# ESC.net
KiCad netlist of a schematic drawn in Altium Designer
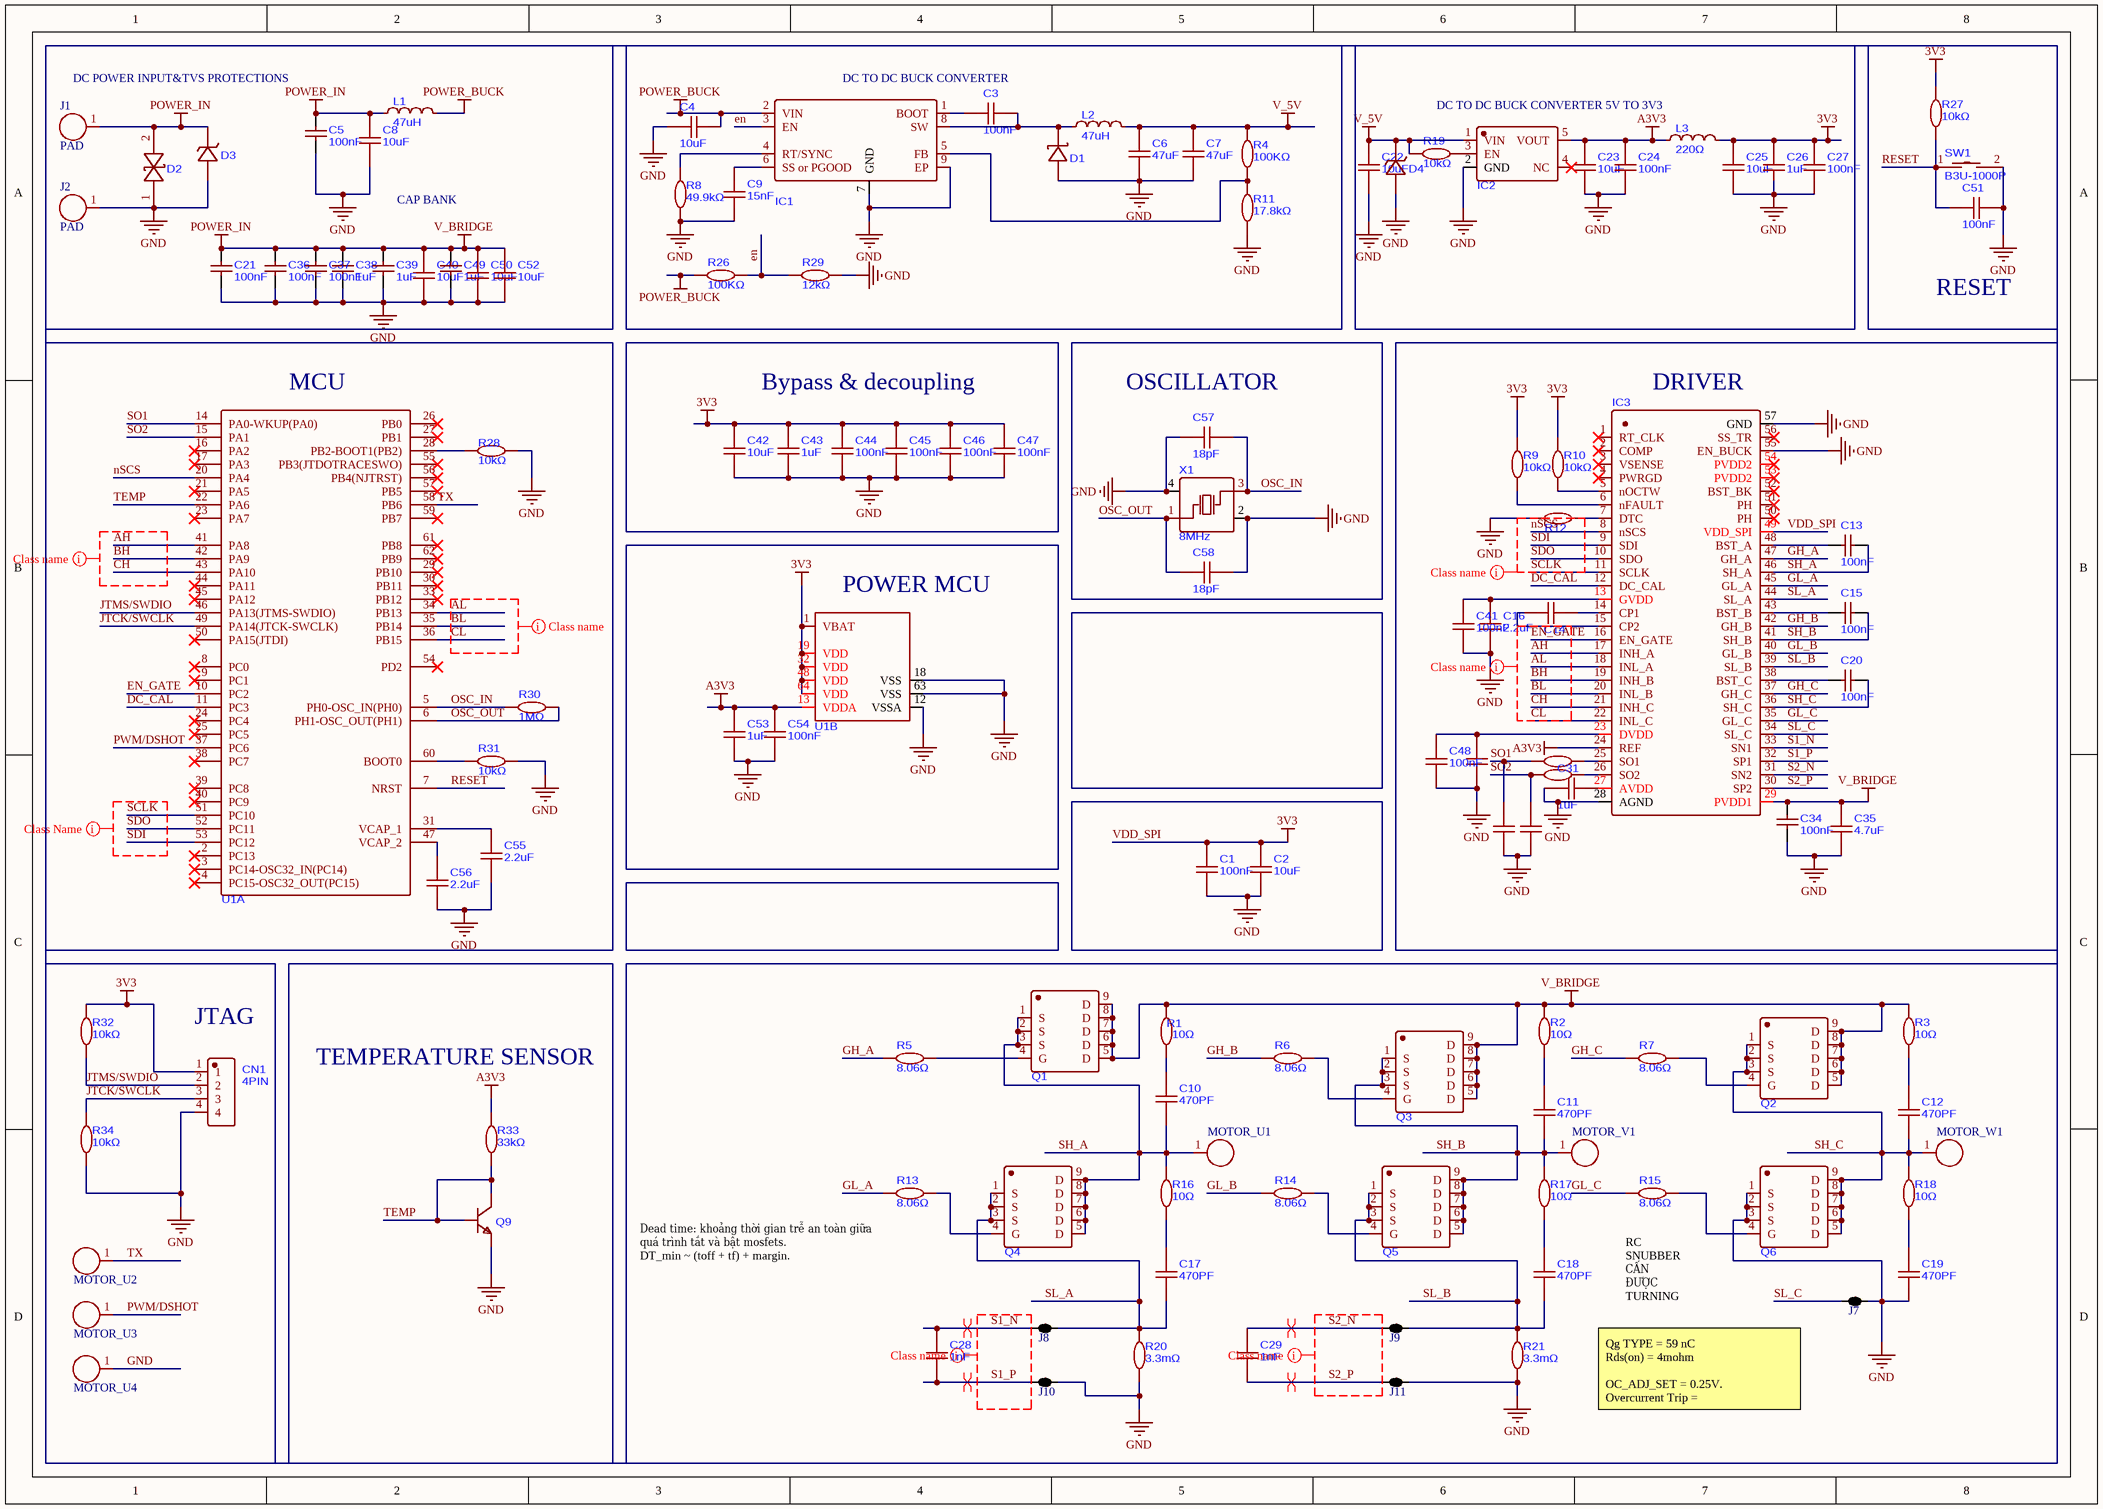
[diagram p0: ESC.SchDoc]

(export (version "E")
  (design (tool "Eeschema 10.0.6"))
  (components
    (comp (ref "C1")
      (value "100nF")
      (footprint "C0603")
      (description "100nF ±10% 50V Ceramic Capacitor X7R 0603")
      (libsource (lib "ESC") (part "CC0603KRX7R9BB104"))
    )
    (comp (ref "C2")
      (value "10uF")
      (footprint "C0603")
      (description "10uF ±10% 10V Ceramic Capacitor X5R 0603")
      (libsource (lib "ESC") (part "CL10A106KP8NNNC"))
    )
    (comp (ref "C3")
      (value "100nF")
      (footprint "C0603")
      (description "100nF ±10% 50V Ceramic Capacitor X7R 0603")
      (libsource (lib "ESC") (part "CC0603KRX7R9BB104"))
    )
    (comp (ref "C4")
      (value "10uF")
      (footprint "C1206")
      (description "10uF X6S ±10% 100V 1206 Ceramic Capacitors RoHS")
      (libsource (lib "ESC") (part "C3216X6S2A106KT0A0E"))
    )
    (comp (ref "C5")
      (value "100nF")
      (footprint "C0805")
      (description "100nF ±10% 100V Ceramic Capacitor X7R 0805")
      (libsource (lib "ESC") (part "CL21B104KCFNNNE"))
    )
    (comp (ref "C6")
      (value "47uF")
      (footprint "C0603")
      (description "47uF ±20% 10V Ceramic Capacitor X5R 0805")
      (libsource (lib "ESC") (part "GRM21BR61A476ME15L_1"))
    )
    (comp (ref "C7")
      (value "47uF")
      (footprint "C0603")
      (description "47uF ±20% 10V Ceramic Capacitor X5R 0805")
      (libsource (lib "ESC") (part "GRM21BR61A476ME15L_1"))
    )
    (comp (ref "C8")
      (value "10uF")
      (footprint "C1206")
      (description "10uF X6S ±10% 100V 1206 Ceramic Capacitors RoHS")
      (libsource (lib "ESC") (part "C3216X6S2A106KT0A0E"))
    )
    (comp (ref "C9")
      (value "15nF")
      (footprint "C0603")
      (description "10uF ±10% 10V Ceramic Capacitor X5R 0603")
      (libsource (lib "ESC") (part "CC0603KRX7R9BB153"))
    )
    (comp (ref "C10")
      (value "470PF")
      (footprint "C0805")
      (description "10nF ±10% 100V Ceramic Capacitor X7R 0805")
      (libsource (lib "ESC") (part "CC0805KRX7R0BB103"))
    )
    (comp (ref "C11")
      (value "470PF")
      (footprint "C0805")
      (description "10nF ±10% 100V Ceramic Capacitor X7R 0805")
      (libsource (lib "ESC") (part "CC0805KRX7R0BB103"))
    )
    (comp (ref "C12")
      (value "470PF")
      (footprint "C0805")
      (description "10nF ±10% 100V Ceramic Capacitor X7R 0805")
      (libsource (lib "ESC") (part "CC0805KRX7R0BB103"))
    )
    (comp (ref "C13")
      (value "100nF")
      (footprint "C0805")
      (description "100nF ±10% 100V Ceramic Capacitor X7R 0805")
      (libsource (lib "ESC") (part "CL21B104KCFNNNE"))
    )
    (comp (ref "C14")
      (value "220nF")
      (footprint "C0603")
      (description "220nF ±10% 25V Ceramic Capacitor X7R 0603")
      (libsource (lib "ESC") (part "CL10B224KA8NNNC"))
    )
    (comp (ref "C15")
      (value "100nF")
      (footprint "C0805")
      (description "100nF ±10% 100V Ceramic Capacitor X7R 0805")
      (libsource (lib "ESC") (part "CL21B104KCFNNNE"))
    )
    (comp (ref "C16")
      (value "2.2uF")
      (footprint "C0603")
      (description "2.2uF X5R ±10% 25V 0603 Ceramic Capacitors RoHS")
      (libsource (lib "ESC") (part "CC0603X5R25V225KN"))
    )
    (comp (ref "C17")
      (value "470PF")
      (footprint "C0805")
      (description "10nF ±10% 100V Ceramic Capacitor X7R 0805")
      (libsource (lib "ESC") (part "CC0805KRX7R0BB103"))
    )
    (comp (ref "C18")
      (value "470PF")
      (footprint "C0805")
      (description "10nF ±10% 100V Ceramic Capacitor X7R 0805")
      (libsource (lib "ESC") (part "CC0805KRX7R0BB103"))
    )
    (comp (ref "C19")
      (value "470PF")
      (footprint "C0805")
      (description "10nF ±10% 100V Ceramic Capacitor X7R 0805")
      (libsource (lib "ESC") (part "CC0805KRX7R0BB103"))
    )
    (comp (ref "C20")
      (value "100nF")
      (footprint "C0805")
      (description "100nF ±10% 100V Ceramic Capacitor X7R 0805")
      (libsource (lib "ESC") (part "CL21B104KCFNNNE"))
    )
    (comp (ref "C21")
      (value "100nF")
      (footprint "C0805")
      (description "100nF ±10% 100V Ceramic Capacitor X7R 0805")
      (libsource (lib "ESC") (part "CL21B104KCFNNNE"))
    )
    (comp (ref "C22")
      (value "10uF")
      (footprint "C0603")
      (description "10uF ±10% 10V Ceramic Capacitor X5R 0603")
      (libsource (lib "ESC") (part "CL10A106KP8NNNC"))
    )
    (comp (ref "C23")
      (value "10uF")
      (footprint "C0603")
      (description "10uF ±10% 10V Ceramic Capacitor X5R 0603")
      (libsource (lib "ESC") (part "CL10A106KP8NNNC"))
    )
    (comp (ref "C24")
      (value "100nF")
      (footprint "C0603")
      (description "100nF ±10% 50V Ceramic Capacitor X7R 0603")
      (libsource (lib "ESC") (part "CC0603KRX7R9BB104"))
    )
    (comp (ref "C25")
      (value "10uF")
      (footprint "C0603")
      (description "10uF ±10% 10V Ceramic Capacitor X5R 0603")
      (libsource (lib "ESC") (part "CL10A106KP8NNNC"))
    )
    (comp (ref "C26")
      (value "1uF")
      (footprint "C0603")
      (description "1uF ±10% 25V Ceramic Capacitor X7R 0603")
      (libsource (lib "ESC") (part "CL10B105KA8NNNC"))
    )
    (comp (ref "C27")
      (value "100nF")
      (footprint "C0603")
      (description "100nF ±10% 50V Ceramic Capacitor X7R 0603")
      (libsource (lib "ESC") (part "CC0603KRX7R9BB104"))
    )
    (comp (ref "C28")
      (value "1nF")
      (footprint "C0603")
      (description "1nF ±10% 50V Ceramic Capacitor X7R 0603")
      (libsource (lib "ESC") (part "CC0603KRX7R9BB102"))
    )
    (comp (ref "C29")
      (value "1nF")
      (footprint "C0603")
      (description "1nF ±10% 50V Ceramic Capacitor X7R 0603")
      (libsource (lib "ESC") (part "CC0603KRX7R9BB102"))
    )
    (comp (ref "C30")
      (value "1uF")
      (footprint "C0603")
      (description "1uF ±10% 25V Ceramic Capacitor X7R 0603")
      (libsource (lib "ESC") (part "CL10B105KA8NNNC"))
    )
    (comp (ref "C31")
      (value "1uF")
      (footprint "C0603")
      (description "1uF ±10% 25V Ceramic Capacitor X7R 0603")
      (libsource (lib "ESC") (part "CL10B105KA8NNNC"))
    )
    (comp (ref "C32")
      (value "2.2uF")
      (footprint "C0603")
      (description "2.2uF X5R ±10% 25V 0603 Ceramic Capacitors RoHS")
      (libsource (lib "ESC") (part "CC0603X5R25V225KN"))
    )
    (comp (ref "C33")
      (value "2.2uF")
      (footprint "C0603")
      (description "2.2uF X5R ±10% 25V 0603 Ceramic Capacitors RoHS")
      (libsource (lib "ESC") (part "CC0603X5R25V225KN"))
    )
    (comp (ref "C34")
      (value "100nF")
      (footprint "C0805")
      (description "100nF ±10% 100V Ceramic Capacitor X7R 0805")
      (libsource (lib "ESC") (part "CL21B104KCFNNNE"))
    )
    (comp (ref "C35")
      (value "4.7uF")
      (footprint "C0805")
      (description "4.7uF ±10% 100V Ceramic Capacitor X5R 0805")
      (libsource (lib "ESC") (part "CIA0805X5R475K101MT"))
    )
    (comp (ref "C36")
      (value "100nF")
      (footprint "C0805")
      (description "100nF ±10% 100V Ceramic Capacitor X7R 0805")
      (libsource (lib "ESC") (part "CL21B104KCFNNNE"))
    )
    (comp (ref "C37")
      (value "100nF")
      (footprint "C0805")
      (description "100nF ±10% 100V Ceramic Capacitor X7R 0805")
      (libsource (lib "ESC") (part "CL21B104KCFNNNE"))
    )
    (comp (ref "C38")
      (value "1uF")
      (footprint "C0805")
      (description "1uF ±10% 100V Ceramic Capacitor X7R 0805")
      (libsource (lib "ESC") (part "CGA0805X7R105K101MT"))
    )
    (comp (ref "C39")
      (value "1uF")
      (footprint "C0805")
      (description "1uF ±10% 100V Ceramic Capacitor X7R 0805")
      (libsource (lib "ESC") (part "CGA0805X7R105K101MT"))
    )
    (comp (ref "C40")
      (value "10uF")
      (footprint "C1206")
      (description "10uF X6S ±10% 100V 1206 Ceramic Capacitors RoHS")
      (libsource (lib "ESC") (part "C3216X6S2A106KT0A0E"))
    )
    (comp (ref "C41")
      (value "100nF")
      (footprint "C0603")
      (description "100nF ±10% 50V Ceramic Capacitor X7R 0603")
      (libsource (lib "ESC") (part "CC0603KRX7R9BB104"))
    )
    (comp (ref "C42")
      (value "10uF")
      (footprint "C0603")
      (description "10uF ±10% 10V Ceramic Capacitor X5R 0603")
      (libsource (lib "ESC") (part "CL10A106KP8NNNC"))
    )
    (comp (ref "C43")
      (value "1uF")
      (footprint "C0603")
      (description "1uF ±10% 25V Ceramic Capacitor X7R 0603")
      (libsource (lib "ESC") (part "CL10B105KA8NNNC"))
    )
    (comp (ref "C44")
      (value "100nF")
      (footprint "C0603")
      (description "100nF ±10% 50V Ceramic Capacitor X7R 0603")
      (libsource (lib "ESC") (part "CC0603KRX7R9BB104"))
    )
    (comp (ref "C45")
      (value "100nF")
      (footprint "C0603")
      (description "100nF ±10% 50V Ceramic Capacitor X7R 0603")
      (libsource (lib "ESC") (part "CC0603KRX7R9BB104"))
    )
    (comp (ref "C46")
      (value "100nF")
      (footprint "C0603")
      (description "100nF ±10% 50V Ceramic Capacitor X7R 0603")
      (libsource (lib "ESC") (part "CC0603KRX7R9BB104"))
    )
    (comp (ref "C47")
      (value "100nF")
      (footprint "C0603")
      (description "100nF ±10% 50V Ceramic Capacitor X7R 0603")
      (libsource (lib "ESC") (part "CC0603KRX7R9BB104"))
    )
    (comp (ref "C48")
      (value "100nF")
      (footprint "C0603")
      (description "100nF ±10% 50V Ceramic Capacitor X7R 0603")
      (libsource (lib "ESC") (part "CC0603KRX7R9BB104"))
    )
    (comp (ref "C49")
      (value "1uF")
      (footprint "C0805")
      (description "1uF ±10% 100V Ceramic Capacitor X7R 0805")
      (libsource (lib "ESC") (part "CGA0805X7R105K101MT"))
    )
    (comp (ref "C50")
      (value "10uF")
      (footprint "C1206")
      (description "10uF X6S ±10% 100V 1206 Ceramic Capacitors RoHS")
      (libsource (lib "ESC") (part "C3216X6S2A106KT0A0E"))
    )
    (comp (ref "C51")
      (value "100nF")
      (footprint "C0603")
      (description "100nF ±10% 50V Ceramic Capacitor X7R 0603")
      (libsource (lib "ESC") (part "CC0603KRX7R9BB104"))
    )
    (comp (ref "C52")
      (value "10uF")
      (footprint "C1206")
      (description "10uF X6S ±10% 100V 1206 Ceramic Capacitors RoHS")
      (libsource (lib "ESC") (part "C3216X6S2A106KT0A0E"))
    )
    (comp (ref "C53")
      (value "1uF")
      (footprint "C0603")
      (description "1uF ±10% 25V Ceramic Capacitor X7R 0603")
      (libsource (lib "ESC") (part "CL10B105KA8NNNC"))
    )
    (comp (ref "C54")
      (value "100nF")
      (footprint "C0603")
      (description "100nF ±10% 50V Ceramic Capacitor X7R 0603")
      (libsource (lib "ESC") (part "CC0603KRX7R9BB104"))
    )
    (comp (ref "C55")
      (value "2.2uF")
      (footprint "C0603")
      (description "2.2uF X5R ±10% 25V 0603 Ceramic Capacitors RoHS")
      (libsource (lib "ESC") (part "CC0603X5R25V225KN"))
    )
    (comp (ref "C56")
      (value "2.2uF")
      (footprint "C0603")
      (description "2.2uF X5R ±10% 25V 0603 Ceramic Capacitors RoHS")
      (libsource (lib "ESC") (part "CC0603X5R25V225KN"))
    )
    (comp (ref "C57")
      (value "18pF")
      (footprint "C0603")
      (description "18pF ±5% 50V Ceramic Capacitor C0G 0603")
      (libsource (lib "ESC") (part "CL10C180JB8NNNC"))
    )
    (comp (ref "C58")
      (value "18pF")
      (footprint "C0603")
      (description "18pF ±5% 50V Ceramic Capacitor C0G 0603")
      (libsource (lib "ESC") (part "CL10C180JB8NNNC"))
    )
    (comp (ref "CN1")
      (value "4PIN")
      (footprint "HDR-TH_4P-HX-PH254-01-04-Z-L11.5")
      (libsource (lib "ESC") (part "HX PH254-01-04-Z-L11.5 STRAIGHT PIN HEADER"))
    )
    (comp (ref "D1")
      (value "DIODE SCHOTTKY 100V SMA(DO-214AC)")
      (footprint "SMA_L4.3-W2.6-LS5.2-RD")
      (description "Diode 100V 2A Surface Mount SMA(DO-214AC)")
      (libsource (lib "ESC") (part "SS210"))
    )
    (comp (ref "D2")
      (value "TVS DIODE 54VWM 87.1VC DO-214AB(SMCJ)")
      (footprint "SMB_L4.6-W3.6-LS5.3-BI")
      (description "87.1VC Clamp 17.2A Ipp TVS DIODE DO-214AB(SMCJ)")
      (libsource (lib "ESC") (part "VISHAY SMCJ54A-E3/57T"))
    )
    (comp (ref "D3")
      (value "DIODE ZENER 56V 500mW SOD-123W")
      (footprint "SOD-123_L2.8-W1.8-LS3.7-RD")
      (description "Zener Diode Independent 56V 500mW Surface Mount SOD-123W")
      (libsource (lib "ESC") (part "BZT52C56"))
    )
    (comp (ref "D4")
      (value "DIODE ZENER 5.6V 500mW LL-34")
      (footprint "LL-34_L3.5-W1.5-RD")
      (description "Zener Diode Independent 5.6V 500mW Surface Mount LL-34")
      (libsource (lib "ESC") (part "ZMM5V6_C707195"))
    )
    (comp (ref "IC1")
      (value "60V 3A Step-Down Converter")
      (footprint "SOIC-8_L4.9-W3.9-P1.27-LS6.0-BL-EP2.3")
      (libsource (lib "ESC") (part "LMR16030SDDAR"))
    )
    (comp (ref "IC2")
      (value "500mA Low-Noise LDo Voltage Regulator")
      (footprint "SOT-23-5_L2.9-W1.6-P0.95-LS2.8-BR")
      (description "3.3V 16V Positive Fixed SOT-23-5 Voltage Regulators - Linear, Low Drop Out (LDO) Regulators RoHS")
      (libsource (lib "ESC") (part "SPX3819M5-L-3-3"))
    )
    (comp (ref "IC3")
      (value "DRV8301 Three-Phase Gate Driver With Dual Current Shunt Amplifiers and Buck Regulator")
      (footprint "HTSSOP-56_L14.0-W6.0-P0.50-LS8.1-BL-EP")
      (description "MOSFET 1.7A 2.3A HTSSOP-56-EP-6mm Motor Drivers, Controllers RoHS")
      (libsource (lib "ESC") (part "DRV8301DCA"))
    )
    (comp (ref "J1") (value "PAD") (footprint "PAD") (libsource (lib "ESC") (part "PAD")))
    (comp (ref "J2") (value "PAD") (footprint "PAD") (libsource (lib "ESC") (part "PAD")))
    (comp (ref "J7")
      (value "2 way net tie junction")
      (footprint "2way_LP")
      (libsource (lib "ESC") (part "2way"))
    )
    (comp (ref "J8")
      (value "2 way net tie junction")
      (footprint "2way_LP")
      (libsource (lib "ESC") (part "2way"))
    )
    (comp (ref "J9")
      (value "2 way net tie junction")
      (footprint "2way_LP")
      (libsource (lib "ESC") (part "2way"))
    )
    (comp (ref "J10")
      (value "2 way net tie junction")
      (footprint "2way_LP")
      (libsource (lib "ESC") (part "2way"))
    )
    (comp (ref "J11")
      (value "2 way net tie junction")
      (footprint "2way_LP")
      (libsource (lib "ESC") (part "2way"))
    )
    (comp (ref "L1")
      (value "47uH")
      (footprint "IND-SMD_L5.0-W5.0_FNR50XXS")
      (description "1.15A 47uH ±20% 1.2A 354mΩ Magnetic Shielded Inductor SMD,5x5mm Fixed Inductors RoHS")
      (libsource (lib "ESC") (part "FNR5040S470MT"))
    )
    (comp (ref "L2")
      (value "47uH")
      (footprint "IND-SMD_L5.0-W5.0_FNR50XXS")
      (description "1.15A 47uH ±20% 1.2A 354mΩ Magnetic Shielded Inductor SMD,5x5mm Fixed Inductors RoHS")
      (libsource (lib "ESC") (part "FNR5040S470MT"))
    )
    (comp (ref "L3")
      (value "220Ω")
      (footprint "C0805")
      (description "220Ω@100MHz 1 Line Ferrite Bead 0805 2A 45mΩ")
      (libsource (lib "ESC") (part "BLM21PG221SN1D"))
    )
    (comp (ref "MOTOR_U1") (value "PAD") (footprint "PAD") (libsource (lib "ESC") (part "PAD")))
    (comp (ref "MOTOR_U2") (value "PAD") (footprint "PAD") (libsource (lib "ESC") (part "PAD")))
    (comp (ref "MOTOR_U3") (value "PAD") (footprint "PAD") (libsource (lib "ESC") (part "PAD")))
    (comp (ref "MOTOR_U4") (value "PAD") (footprint "PAD") (libsource (lib "ESC") (part "PAD")))
    (comp (ref "MOTOR_V1") (value "PAD") (footprint "PAD") (libsource (lib "ESC") (part "PAD")))
    (comp (ref "MOTOR_W1") (value "PAD") (footprint "PAD") (libsource (lib "ESC") (part "PAD")))
    (comp (ref "Q1")
      (value "MOSFET N-CH 80V 100A SOP-8-Advance")
      (footprint "SOP-8_L5.0-W5.0-P1.27-LS6.0_TPH4R008NH-L1Q")
      (description "N-Channel 80V 100A 78W SOP-8-Advance")
      (libsource (lib "ESC") (part "TPH4R008NH,L1Q(M"))
    )
    (comp (ref "Q2")
      (value "MOSFET N-CH 80V 100A SOP-8-Advance")
      (footprint "SOP-8_L5.0-W5.0-P1.27-LS6.0_TPH4R008NH-L1Q")
      (description "N-Channel 80V 100A 78W SOP-8-Advance")
      (libsource (lib "ESC") (part "TPH4R008NH,L1Q(M"))
    )
    (comp (ref "Q3")
      (value "MOSFET N-CH 80V 100A SOP-8-Advance")
      (footprint "SOP-8_L5.0-W5.0-P1.27-LS6.0_TPH4R008NH-L1Q")
      (description "N-Channel 80V 100A 78W SOP-8-Advance")
      (libsource (lib "ESC") (part "TPH4R008NH,L1Q(M"))
    )
    (comp (ref "Q4")
      (value "MOSFET N-CH 80V 100A SOP-8-Advance")
      (footprint "SOP-8_L5.0-W5.0-P1.27-LS6.0_TPH4R008NH-L1Q")
      (description "N-Channel 80V 100A 78W SOP-8-Advance")
      (libsource (lib "ESC") (part "TPH4R008NH,L1Q(M"))
    )
    (comp (ref "Q5")
      (value "MOSFET N-CH 80V 100A SOP-8-Advance")
      (footprint "SOP-8_L5.0-W5.0-P1.27-LS6.0_TPH4R008NH-L1Q")
      (description "N-Channel 80V 100A 78W SOP-8-Advance")
      (libsource (lib "ESC") (part "TPH4R008NH,L1Q(M"))
    )
    (comp (ref "Q6")
      (value "MOSFET N-CH 80V 100A SOP-8-Advance")
      (footprint "SOP-8_L5.0-W5.0-P1.27-LS6.0_TPH4R008NH-L1Q")
      (description "N-Channel 80V 100A 78W SOP-8-Advance")
      (libsource (lib "ESC") (part "TPH4R008NH,L1Q(M"))
    )
    (comp (ref "Q9")
      (value "TRANS NPN 40V 200mA SOT-416")
      (footprint "SC-75-3_L1.6-W0.8-P1.00-LS1.6-BR")
      (description "Bipolar (BJT) Transistor NPN 40V 200mA 300MHz 200mW Surface Mount SOT-416")
      (libsource (lib "ESC") (part "MMBT3904TT1G"))
    )
    (comp (ref "R1")
      (value "10Ω")
      (footprint "R0805")
      (description "10Ω 500mW Thick Film Resistor ±100ppm/℃ ±1% 0805 Chip Resistor - Surface Mount RoHS")
      (libsource (lib "ESC") (part "CRCW080510R0FKEAHP"))
    )
    (comp (ref "R2")
      (value "10Ω")
      (footprint "R0805")
      (description "10Ω 500mW Thick Film Resistor ±100ppm/℃ ±1% 0805 Chip Resistor - Surface Mount RoHS")
      (libsource (lib "ESC") (part "CRCW080510R0FKEAHP"))
    )
    (comp (ref "R3")
      (value "10Ω")
      (footprint "R0805")
      (description "10Ω 500mW Thick Film Resistor ±100ppm/℃ ±1% 0805 Chip Resistor - Surface Mount RoHS")
      (libsource (lib "ESC") (part "CRCW080510R0FKEAHP"))
    )
    (comp (ref "R4")
      (value "100KΩ")
      (footprint "R0603")
      (description "100mW 100kΩ 75V Thick Film Resistor ±100ppm/℃ ±1% 0603 Chip Resistor - Surface Mount RoHS")
      (libsource (lib "ESC") (part "RC0603FR-07100KL"))
    )
    (comp (ref "R5")
      (value "8.06Ω")
      (footprint "R1206")
      (description "8.06Ω ±1% 250mW 1206 Thick Film Resistor")
      (libsource (lib "ESC") (part "FRC1206F8R06TS"))
    )
    (comp (ref "R6")
      (value "8.06Ω")
      (footprint "R1206")
      (description "8.06Ω ±1% 250mW 1206 Thick Film Resistor")
      (libsource (lib "ESC") (part "FRC1206F8R06TS"))
    )
    (comp (ref "R7")
      (value "8.06Ω")
      (footprint "R1206")
      (description "8.06Ω ±1% 250mW 1206 Thick Film Resistor")
      (libsource (lib "ESC") (part "FRC1206F8R06TS"))
    )
    (comp (ref "R8")
      (value "49.9kΩ")
      (footprint "R0603")
      (description "100mW 49.9kΩ 75V Thick Film Resistor ±100ppm/℃ ±1% 0603 Chip Resistor - Surface Mount RoHS")
      (libsource (lib "ESC") (part "RC0603FR-0749K9L"))
    )
    (comp (ref "R9")
      (value "10kΩ")
      (footprint "R0603")
      (description "100mW 10kΩ 75V ±100ppm/℃ Thick Film Resistor ±1% 0603 Chip Resistor - Surface Mount ROHS")
      (libsource (lib "ESC") (part "RC0603FR-0710KL"))
    )
    (comp (ref "R10")
      (value "10kΩ")
      (footprint "R0603")
      (description "100mW 10kΩ 75V ±100ppm/℃ Thick Film Resistor ±1% 0603 Chip Resistor - Surface Mount ROHS")
      (libsource (lib "ESC") (part "RC0603FR-0710KL"))
    )
    (comp (ref "R11")
      (value "17.8kΩ")
      (footprint "R0603")
      (description "17.8kΩ ±1% 100mW 0603 Thick Film Resistor")
      (libsource (lib "ESC") (part "0603WAF1782T5E"))
    )
    (comp (ref "R12")
      (value "24.9KΩ")
      (footprint "R0603")
      (description "24.9kΩ ±1% 100mW 0603 Thick Film Resistor")
      (libsource (lib "ESC") (part "FRC0603F2492TS"))
    )
    (comp (ref "R13")
      (value "8.06Ω")
      (footprint "R1206")
      (description "8.06Ω ±1% 250mW 1206 Thick Film Resistor")
      (libsource (lib "ESC") (part "FRC1206F8R06TS"))
    )
    (comp (ref "R14")
      (value "8.06Ω")
      (footprint "R1206")
      (description "8.06Ω ±1% 250mW 1206 Thick Film Resistor")
      (libsource (lib "ESC") (part "FRC1206F8R06TS"))
    )
    (comp (ref "R15")
      (value "8.06Ω")
      (footprint "R1206")
      (description "8.06Ω ±1% 250mW 1206 Thick Film Resistor")
      (libsource (lib "ESC") (part "FRC1206F8R06TS"))
    )
    (comp (ref "R16")
      (value "10Ω")
      (footprint "R0805")
      (description "10Ω 500mW Thick Film Resistor ±100ppm/℃ ±1% 0805 Chip Resistor - Surface Mount RoHS")
      (libsource (lib "ESC") (part "CRCW080510R0FKEAHP"))
    )
    (comp (ref "R17")
      (value "10Ω")
      (footprint "R0805")
      (description "10Ω 500mW Thick Film Resistor ±100ppm/℃ ±1% 0805 Chip Resistor - Surface Mount RoHS")
      (libsource (lib "ESC") (part "CRCW080510R0FKEAHP"))
    )
    (comp (ref "R18")
      (value "10Ω")
      (footprint "R0805")
      (description "10Ω 500mW Thick Film Resistor ±100ppm/℃ ±1% 0805 Chip Resistor - Surface Mount RoHS")
      (libsource (lib "ESC") (part "CRCW080510R0FKEAHP"))
    )
    (comp (ref "R19")
      (value "10kΩ")
      (footprint "R0603")
      (description "100mW 10kΩ 75V ±100ppm/℃ Thick Film Resistor ±1% 0603 Chip Resistor - Surface Mount ROHS")
      (libsource (lib "ESC") (part "RC0603FR-0710KL"))
    )
    (comp (ref "R20")
      (value "3.3mΩ")
      (footprint "R2512")
      (description "3.3mΩ 3W Current Sense Resistor ±1% ±150ppm/℃ 2512 Chip Resistor - Surface Mount RoHS")
      (libsource (lib "ESC") (part "WSLP25123L300FEA"))
    )
    (comp (ref "R21")
      (value "3.3mΩ")
      (footprint "R2512")
      (description "3.3mΩ 3W Current Sense Resistor ±1% ±150ppm/℃ 2512 Chip Resistor - Surface Mount RoHS")
      (libsource (lib "ESC") (part "WSLP25123L300FEA"))
    )
    (comp (ref "R22")
      (value "56Ω")
      (footprint "R0603")
      (description "56Ω ±1% 100mW 0603 Thick Film Resistor")
      (libsource (lib "ESC") (part "FRC0603F56R0TS"))
    )
    (comp (ref "R23")
      (value "56Ω")
      (footprint "R0603")
      (description "56Ω ±1% 100mW 0603 Thick Film Resistor")
      (libsource (lib "ESC") (part "FRC0603F56R0TS"))
    )
    (comp (ref "R26")
      (value "100KΩ")
      (footprint "R0603")
      (description "100mW 100kΩ 75V Thick Film Resistor ±100ppm/℃ ±1% 0603 Chip Resistor - Surface Mount RoHS")
      (libsource (lib "ESC") (part "RC0603FR-07100KL"))
    )
    (comp (ref "R27")
      (value "10kΩ")
      (footprint "R0603")
      (description "100mW 10kΩ 75V ±100ppm/℃ Thick Film Resistor ±1% 0603 Chip Resistor - Surface Mount ROHS")
      (libsource (lib "ESC") (part "RC0603FR-0710KL"))
    )
    (comp (ref "R28")
      (value "10kΩ")
      (footprint "R0603")
      (description "100mW 10kΩ 75V ±100ppm/℃ Thick Film Resistor ±1% 0603 Chip Resistor - Surface Mount ROHS")
      (libsource (lib "ESC") (part "RC0603FR-0710KL"))
    )
    (comp (ref "R29")
      (value "12kΩ")
      (footprint "R0603")
      (description "12kΩ 100mW 75V Thick Film Resistor ±100ppm/℃ ±1% 0603 Chip Resistor - Surface Mount RoHS")
      (libsource (lib "ESC") (part "RC0603FR-0712KL"))
    )
    (comp (ref "R30")
      (value "1MΩ")
      (footprint "R0603")
      (description "100mW 1MΩ 75V Thick Film Resistor ±100ppm/℃ ±1% 0603 Chip Resistor - Surface Mount RoHS")
      (libsource (lib "ESC") (part "RC0603FR-071ML"))
    )
    (comp (ref "R31")
      (value "10kΩ")
      (footprint "R0603")
      (description "100mW 10kΩ 75V ±100ppm/℃ Thick Film Resistor ±1% 0603 Chip Resistor - Surface Mount ROHS")
      (libsource (lib "ESC") (part "RC0603FR-0710KL"))
    )
    (comp (ref "R32")
      (value "10kΩ")
      (footprint "R0603")
      (description "100mW 10kΩ 75V ±100ppm/℃ Thick Film Resistor ±1% 0603 Chip Resistor - Surface Mount ROHS")
      (libsource (lib "ESC") (part "RC0603FR-0710KL"))
    )
    (comp (ref "R33")
      (value "33kΩ")
      (footprint "R0603")
      (description "100mW 33kΩ 75V Thick Film Resistor ±100ppm/℃ ±1% 0603 Chip Resistor - Surface Mount RoHS")
      (libsource (lib "ESC") (part "RC0603FR-0733KL"))
    )
    (comp (ref "R34")
      (value "10kΩ")
      (footprint "R0603")
      (description "100mW 10kΩ 75V ±100ppm/℃ Thick Film Resistor ±1% 0603 Chip Resistor - Surface Mount ROHS")
      (libsource (lib "ESC") (part "RC0603FR-0710KL"))
    )
    (comp (ref "SW1")
      (value "B3U-1000P")
      (footprint "KEY-SMD_B3U-1000PM")
      (description "12V 2.5mm Round Button 3mm SPST 50mA SMD,3x2.5mm Tactile Switches ROHS")
      (libsource (lib "ESC") (part "B3U-1000P"))
    )
    (comp (ref "U1")
      (value "ARM Cortex-M4 32b MCU+FPU, 210DMIPS, up to 1MB Flash/192+4KB RAM, USB OTG HS/FS, Ethernet, 17 TIMs, 3 ADCs, 15 comm. interfaces & camera")
      (footprint "LQFP-64_L10.0-W10.0-P0.50-LS12.0-BL")
      (description "ARM Cortex-M4 32 Bit 168MHz 51 LQFP-64(10x10) Microcontrollers RoHS")
      (libsource (lib "") (part "STM32F405RGT6_1"))
    )
    (comp (ref "X1")
      (value "8MHz")
      (footprint "OSC-SMD_4P-L5.0-W3.2-BL")
      (description "Crystal 8MHz ±10ppm 10pF 200Ω SMD5032-4P")
      (libsource (lib "ESC") (part "ABM3B-8.000MHZ-10-1-U-T"))
    )
  )
  (nets
    (net (code "1") (name "/AH") (class "Default")
      (node (ref "IC3") (pin "17") (pinfunction "INH_A_17") (pintype "passive"))
      (node (ref "U1") (pin "41") (pinfunction "PA8_41") (pintype "passive"))
    )
    (net (code "2") (name "/AL") (class "Default")
      (node (ref "IC3") (pin "18") (pinfunction "INL_A_18") (pintype "passive"))
      (node (ref "U1") (pin "34") (pinfunction "PB13_34") (pintype "passive"))
    )
    (net (code "3") (name "/BH") (class "Default")
      (node (ref "IC3") (pin "19") (pinfunction "INH_B_19") (pintype "passive"))
      (node (ref "U1") (pin "42") (pinfunction "PA9_42") (pintype "passive"))
    )
    (net (code "4") (name "/BL") (class "Default")
      (node (ref "IC3") (pin "20") (pinfunction "INL_B_20") (pintype "passive"))
      (node (ref "U1") (pin "35") (pinfunction "PB14_35") (pintype "passive"))
    )
    (net (code "5") (name "/CH") (class "Default")
      (node (ref "IC3") (pin "21") (pinfunction "INH_C_21") (pintype "passive"))
      (node (ref "U1") (pin "43") (pinfunction "PA10_43") (pintype "passive"))
    )
    (net (code "6") (name "/CL") (class "Default")
      (node (ref "IC3") (pin "22") (pinfunction "INL_C_22") (pintype "passive"))
      (node (ref "U1") (pin "36") (pinfunction "PB15_36") (pintype "passive"))
    )
    (net (code "7") (name "/DC_CAL") (class "Default")
      (node (ref "IC3") (pin "12") (pinfunction "DC_CAL_12") (pintype "passive"))
      (node (ref "U1") (pin "11") (pinfunction "PC3_11") (pintype "passive"))
    )
    (net (code "8") (name "/EN_GATE") (class "Default")
      (node (ref "IC3") (pin "16") (pinfunction "EN_GATE_16") (pintype "passive"))
      (node (ref "U1") (pin "10") (pinfunction "PC2_10") (pintype "passive"))
    )
    (net (code "9") (name "/GH_A") (class "Default")
      (node (ref "IC3") (pin "47") (pinfunction "GH_A_47") (pintype "passive"))
      (node (ref "R5") (pin "1") (pinfunction "1_1") (pintype "passive"))
    )
    (net (code "10") (name "/GH_B") (class "Default")
      (node (ref "IC3") (pin "42") (pinfunction "GH_B_42") (pintype "passive"))
      (node (ref "R6") (pin "1") (pinfunction "1_1") (pintype "passive"))
    )
    (net (code "11") (name "/GH_C") (class "Default")
      (node (ref "IC3") (pin "37") (pinfunction "GH_C_37") (pintype "passive"))
      (node (ref "R7") (pin "1") (pinfunction "1_1") (pintype "passive"))
    )
    (net (code "12") (name "/GL_A") (class "Default")
      (node (ref "IC3") (pin "45") (pinfunction "GL_A_45") (pintype "passive"))
      (node (ref "R13") (pin "1") (pinfunction "1_1") (pintype "passive"))
    )
    (net (code "13") (name "/GL_B") (class "Default")
      (node (ref "IC3") (pin "40") (pinfunction "GL_B_40") (pintype "passive"))
      (node (ref "R14") (pin "1") (pinfunction "1_1") (pintype "passive"))
    )
    (net (code "14") (name "/GL_C") (class "Default")
      (node (ref "IC3") (pin "35") (pinfunction "GL_C_35") (pintype "passive"))
      (node (ref "R15") (pin "1") (pinfunction "1_1") (pintype "passive"))
    )
    (net (code "15") (name "/JTCK{slash}SWCLK") (class "Default")
      (node (ref "CN1") (pin "3") (pinfunction "3_3") (pintype "passive"))
      (node (ref "R34") (pin "2") (pinfunction "2_2") (pintype "passive"))
      (node (ref "U1") (pin "49") (pinfunction "PA14(JTCK-SWCLK)_49") (pintype "passive"))
    )
    (net (code "16") (name "/JTMS{slash}SWDIO") (class "Default")
      (node (ref "CN1") (pin "2") (pinfunction "2_2") (pintype "passive"))
      (node (ref "R32") (pin "1") (pinfunction "1_1") (pintype "passive"))
      (node (ref "U1") (pin "46") (pinfunction "PA13(JTMS-SWDIO)_46") (pintype "passive"))
    )
    (net (code "17") (name "/OSC_IN") (class "Default")
      (node (ref "C57") (pin "2") (pinfunction "2_2") (pintype "passive"))
      (node (ref "R30") (pin "2") (pinfunction "2_2") (pintype "passive"))
      (node (ref "U1") (pin "5") (pinfunction "PH0-OSC_IN(PH0)_5") (pintype "passive"))
      (node (ref "X1") (pin "3") (pinfunction "OSC2_3") (pintype "passive"))
    )
    (net (code "18") (name "/OSC_OUT") (class "Default")
      (node (ref "C58") (pin "1") (pinfunction "1_1") (pintype "passive"))
      (node (ref "R30") (pin "1") (pinfunction "1_1") (pintype "passive"))
      (node (ref "U1") (pin "6") (pinfunction "PH1-OSC_OUT(PH1)_6") (pintype "passive"))
      (node (ref "X1") (pin "1") (pinfunction "OSC1_1") (pintype "passive"))
    )
    (net (code "19") (name "/PWM{slash}DSHOT") (class "Default")
      (node (ref "MOTOR_U3") (pin "1") (pintype "passive"))
      (node (ref "U1") (pin "37") (pinfunction "PC6_37") (pintype "passive"))
    )
    (net (code "20") (name "/RESET") (class "Default")
      (node (ref "C51") (pin "1") (pinfunction "1_1") (pintype "passive"))
      (node (ref "R27") (pin "1") (pinfunction "1_1") (pintype "passive"))
      (node (ref "SW1") (pin "1") (pinfunction "1_1") (pintype "passive"))
      (node (ref "U1") (pin "7") (pinfunction "NRST_7") (pintype "passive"))
    )
    (net (code "21") (name "/S1_N") (class "Default")
      (node (ref "C28") (pin "2") (pinfunction "2_2") (pintype "passive"))
      (node (ref "IC3") (pin "33") (pinfunction "SN1_33") (pintype "passive"))
      (node (ref "J8") (pin "1") (pinfunction "1_1") (pintype "passive"))
    )
    (net (code "22") (name "/S1_P") (class "Default")
      (node (ref "C28") (pin "1") (pinfunction "1_1") (pintype "passive"))
      (node (ref "IC3") (pin "32") (pinfunction "SP1_32") (pintype "passive"))
      (node (ref "J10") (pin "1") (pinfunction "1_1") (pintype "passive"))
    )
    (net (code "23") (name "/S2_N") (class "Default")
      (node (ref "C29") (pin "2") (pinfunction "2_2") (pintype "passive"))
      (node (ref "IC3") (pin "31") (pinfunction "SN2_31") (pintype "passive"))
      (node (ref "J9") (pin "1") (pinfunction "1_1") (pintype "passive"))
    )
    (net (code "24") (name "/S2_P") (class "Default")
      (node (ref "C29") (pin "1") (pinfunction "1_1") (pintype "passive"))
      (node (ref "IC3") (pin "30") (pinfunction "SP2_30") (pintype "passive"))
      (node (ref "J11") (pin "1") (pinfunction "1_1") (pintype "passive"))
    )
    (net (code "25") (name "/SCLK") (class "Default")
      (node (ref "IC3") (pin "11") (pinfunction "SCLK_11") (pintype "passive"))
      (node (ref "U1") (pin "51") (pinfunction "PC10_51") (pintype "passive"))
    )
    (net (code "26") (name "/SDI") (class "Default")
      (node (ref "IC3") (pin "9") (pinfunction "SDI_9") (pintype "passive"))
      (node (ref "U1") (pin "53") (pinfunction "PC12_53") (pintype "passive"))
    )
    (net (code "27") (name "/SDO") (class "Default")
      (node (ref "IC3") (pin "10") (pinfunction "SDO_10") (pintype "passive"))
      (node (ref "U1") (pin "52") (pinfunction "PC11_52") (pintype "passive"))
    )
    (net (code "28") (name "/SH_A") (class "Default")
      (node (ref "C10") (pin "1") (pinfunction "1_1") (pintype "passive"))
      (node (ref "C13") (pin "2") (pinfunction "2_2") (pintype "passive"))
      (node (ref "IC3") (pin "46") (pinfunction "SH_A_46") (pintype "passive"))
      (node (ref "MOTOR_U1") (pin "1") (pintype "passive"))
      (node (ref "Q1") (pin "1") (pinfunction "S_1") (pintype "passive"))
      (node (ref "Q1") (pin "2") (pinfunction "S_2") (pintype "passive"))
      (node (ref "Q1") (pin "3") (pinfunction "S_3") (pintype "passive"))
      (node (ref "Q4") (pin "5") (pinfunction "D_5") (pintype "passive"))
      (node (ref "Q4") (pin "6") (pinfunction "D_6") (pintype "passive"))
      (node (ref "Q4") (pin "7") (pinfunction "D_7") (pintype "passive"))
      (node (ref "Q4") (pin "8") (pinfunction "D_8") (pintype "passive"))
      (node (ref "Q4") (pin "9") (pinfunction "D_9") (pintype "passive"))
      (node (ref "R16") (pin "2") (pinfunction "2_2") (pintype "passive"))
    )
    (net (code "29") (name "/SH_B") (class "Default")
      (node (ref "C11") (pin "1") (pinfunction "1_1") (pintype "passive"))
      (node (ref "C15") (pin "2") (pinfunction "2_2") (pintype "passive"))
      (node (ref "IC3") (pin "41") (pinfunction "SH_B_41") (pintype "passive"))
      (node (ref "MOTOR_V1") (pin "1") (pintype "passive"))
      (node (ref "Q3") (pin "1") (pinfunction "S_1") (pintype "passive"))
      (node (ref "Q3") (pin "2") (pinfunction "S_2") (pintype "passive"))
      (node (ref "Q3") (pin "3") (pinfunction "S_3") (pintype "passive"))
      (node (ref "Q5") (pin "5") (pinfunction "D_5") (pintype "passive"))
      (node (ref "Q5") (pin "6") (pinfunction "D_6") (pintype "passive"))
      (node (ref "Q5") (pin "7") (pinfunction "D_7") (pintype "passive"))
      (node (ref "Q5") (pin "8") (pinfunction "D_8") (pintype "passive"))
      (node (ref "Q5") (pin "9") (pinfunction "D_9") (pintype "passive"))
      (node (ref "R17") (pin "2") (pinfunction "2_2") (pintype "passive"))
    )
    (net (code "30") (name "/SH_C") (class "Default")
      (node (ref "C12") (pin "1") (pinfunction "1_1") (pintype "passive"))
      (node (ref "C20") (pin "2") (pinfunction "2_2") (pintype "passive"))
      (node (ref "IC3") (pin "36") (pinfunction "SH_C_36") (pintype "passive"))
      (node (ref "MOTOR_W1") (pin "1") (pintype "passive"))
      (node (ref "Q2") (pin "1") (pinfunction "S_1") (pintype "passive"))
      (node (ref "Q2") (pin "2") (pinfunction "S_2") (pintype "passive"))
      (node (ref "Q2") (pin "3") (pinfunction "S_3") (pintype "passive"))
      (node (ref "Q6") (pin "5") (pinfunction "D_5") (pintype "passive"))
      (node (ref "Q6") (pin "6") (pinfunction "D_6") (pintype "passive"))
      (node (ref "Q6") (pin "7") (pinfunction "D_7") (pintype "passive"))
      (node (ref "Q6") (pin "8") (pinfunction "D_8") (pintype "passive"))
      (node (ref "Q6") (pin "9") (pinfunction "D_9") (pintype "passive"))
      (node (ref "R18") (pin "2") (pinfunction "2_2") (pintype "passive"))
    )
    (net (code "31") (name "/SL_A") (class "Default")
      (node (ref "C17") (pin "1") (pinfunction "1_1") (pintype "passive"))
      (node (ref "IC3") (pin "44") (pinfunction "SL_A_44") (pintype "passive"))
      (node (ref "J8") (pin "2") (pinfunction "2_2") (pintype "passive"))
      (node (ref "Q4") (pin "1") (pinfunction "S_1") (pintype "passive"))
      (node (ref "Q4") (pin "2") (pinfunction "S_2") (pintype "passive"))
      (node (ref "Q4") (pin "3") (pinfunction "S_3") (pintype "passive"))
      (node (ref "R20") (pin "2") (pinfunction "2_2") (pintype "passive"))
    )
    (net (code "32") (name "/SL_B") (class "Default")
      (node (ref "C18") (pin "1") (pinfunction "1_1") (pintype "passive"))
      (node (ref "IC3") (pin "39") (pinfunction "SL_B_39") (pintype "passive"))
      (node (ref "J9") (pin "2") (pinfunction "2_2") (pintype "passive"))
      (node (ref "Q5") (pin "1") (pinfunction "S_1") (pintype "passive"))
      (node (ref "Q5") (pin "2") (pinfunction "S_2") (pintype "passive"))
      (node (ref "Q5") (pin "3") (pinfunction "S_3") (pintype "passive"))
      (node (ref "R21") (pin "2") (pinfunction "2_2") (pintype "passive"))
    )
    (net (code "33") (name "/SL_C") (class "Default")
      (node (ref "IC3") (pin "34") (pinfunction "SL_C_34") (pintype "passive"))
      (node (ref "J7") (pin "1") (pinfunction "1_1") (pintype "passive"))
    )
    (net (code "34") (name "/SO1") (class "Default")
      (node (ref "C32") (pin "2") (pinfunction "2_2") (pintype "passive"))
      (node (ref "R22") (pin "2") (pinfunction "2_2") (pintype "passive"))
      (node (ref "U1") (pin "14") (pinfunction "PA0-WKUP(PA0)_14") (pintype "passive"))
    )
    (net (code "35") (name "/SO2") (class "Default")
      (node (ref "C33") (pin "2") (pinfunction "2_2") (pintype "passive"))
      (node (ref "R23") (pin "2") (pinfunction "2_2") (pintype "passive"))
      (node (ref "U1") (pin "15") (pinfunction "PA1_15") (pintype "passive"))
    )
    (net (code "36") (name "/TEMP") (class "Default")
      (node (ref "Q9") (pin "1") (pinfunction "B_1") (pintype "passive"))
      (node (ref "Q9") (pin "3") (pinfunction "C_3") (pintype "passive"))
      (node (ref "R33") (pin "1") (pinfunction "1_1") (pintype "passive"))
      (node (ref "U1") (pin "22") (pinfunction "PA6_22") (pintype "passive"))
    )
    (net (code "37") (name "/TX") (class "Default")
      (node (ref "MOTOR_U2") (pin "1") (pintype "passive"))
      (node (ref "U1") (pin "58") (pinfunction "PB6_58") (pintype "passive"))
    )
    (net (code "38") (name "/en") (class "Default")
      (node (ref "IC1") (pin "3") (pinfunction "EN_3") (pintype "passive"))
      (node (ref "R26") (pin "1") (pinfunction "1_1") (pintype "passive"))
      (node (ref "R29") (pin "2") (pinfunction "2_2") (pintype "passive"))
    )
    (net (code "39") (name "/nSCS") (class "Default")
      (node (ref "IC3") (pin "8") (pinfunction "nSCS_8") (pintype "passive"))
      (node (ref "U1") (pin "20") (pinfunction "PA4_20") (pintype "passive"))
    )
    (net (code "40") (name "3V3") (class "Default")
      (node (ref "C1") (pin "2") (pinfunction "2_2") (pintype "passive"))
      (node (ref "C2") (pin "2") (pinfunction "2_2") (pintype "passive"))
      (node (ref "C25") (pin "2") (pinfunction "2_2") (pintype "passive"))
      (node (ref "C26") (pin "2") (pinfunction "2_2") (pintype "passive"))
      (node (ref "C27") (pin "2") (pinfunction "2_2") (pintype "passive"))
      (node (ref "C42") (pin "2") (pinfunction "2_2") (pintype "passive"))
      (node (ref "C43") (pin "2") (pinfunction "2_2") (pintype "passive"))
      (node (ref "C44") (pin "2") (pinfunction "2_2") (pintype "passive"))
      (node (ref "C45") (pin "2") (pinfunction "2_2") (pintype "passive"))
      (node (ref "C46") (pin "2") (pinfunction "2_2") (pintype "passive"))
      (node (ref "C47") (pin "2") (pinfunction "2_2") (pintype "passive"))
      (node (ref "CN1") (pin "1") (pinfunction "1_1") (pintype "passive"))
      (node (ref "IC3") (pin "49") (pinfunction "VDD_SPI_49") (pintype "passive"))
      (node (ref "L3") (pin "2") (pinfunction "2_2") (pintype "passive"))
      (node (ref "R10") (pin "1") (pinfunction "1_1") (pintype "passive"))
      (node (ref "R27") (pin "2") (pinfunction "2_2") (pintype "passive"))
      (node (ref "R32") (pin "2") (pinfunction "2_2") (pintype "passive"))
      (node (ref "R9") (pin "2") (pinfunction "2_2") (pintype "passive"))
      (node (ref "U1") (pin "1") (pinfunction "VBAT_1") (pintype "passive"))
      (node (ref "U1") (pin "19") (pinfunction "VDD_19") (pintype "passive"))
      (node (ref "U1") (pin "32") (pinfunction "VDD_32") (pintype "passive"))
      (node (ref "U1") (pin "48") (pinfunction "VDD_48") (pintype "passive"))
      (node (ref "U1") (pin "64") (pinfunction "VDD_64") (pintype "passive"))
    )
    (net (code "41") (name "A3V3") (class "Default")
      (node (ref "C23") (pin "2") (pinfunction "2_2") (pintype "passive"))
      (node (ref "C24") (pin "2") (pinfunction "2_2") (pintype "passive"))
      (node (ref "C53") (pin "2") (pinfunction "2_2") (pintype "passive"))
      (node (ref "C54") (pin "2") (pinfunction "2_2") (pintype "passive"))
      (node (ref "IC2") (pin "5") (pinfunction "VOUT_5") (pintype "passive"))
      (node (ref "IC3") (pin "24") (pinfunction "REF_24") (pintype "passive"))
      (node (ref "L3") (pin "1") (pinfunction "1_1") (pintype "passive"))
      (node (ref "R33") (pin "2") (pinfunction "2_2") (pintype "passive"))
      (node (ref "U1") (pin "13") (pinfunction "VDDA_13") (pintype "passive"))
    )
    (net (code "42") (name "GND") (class "Default")
      (node (ref "C1") (pin "1") (pinfunction "1_1") (pintype "passive"))
      (node (ref "C16") (pin "1") (pinfunction "1_1") (pintype "passive"))
      (node (ref "C19") (pin "1") (pinfunction "1_1") (pintype "passive"))
      (node (ref "C2") (pin "1") (pinfunction "1_1") (pintype "passive"))
      (node (ref "C21") (pin "1") (pinfunction "1_1") (pintype "passive"))
      (node (ref "C22") (pin "1") (pinfunction "1_1") (pintype "passive"))
      (node (ref "C23") (pin "1") (pinfunction "1_1") (pintype "passive"))
      (node (ref "C24") (pin "1") (pinfunction "1_1") (pintype "passive"))
      (node (ref "C25") (pin "1") (pinfunction "1_1") (pintype "passive"))
      (node (ref "C26") (pin "1") (pinfunction "1_1") (pintype "passive"))
      (node (ref "C27") (pin "1") (pinfunction "1_1") (pintype "passive"))
      (node (ref "C30") (pin "1") (pinfunction "1_1") (pintype "passive"))
      (node (ref "C31") (pin "2") (pinfunction "2_2") (pintype "passive"))
      (node (ref "C32") (pin "1") (pinfunction "1_1") (pintype "passive"))
      (node (ref "C33") (pin "1") (pinfunction "1_1") (pintype "passive"))
      (node (ref "C34") (pin "1") (pinfunction "1_1") (pintype "passive"))
      (node (ref "C35") (pin "1") (pinfunction "1_1") (pintype "passive"))
      (node (ref "C36") (pin "1") (pinfunction "1_1") (pintype "passive"))
      (node (ref "C37") (pin "1") (pinfunction "1_1") (pintype "passive"))
      (node (ref "C38") (pin "1") (pinfunction "1_1") (pintype "passive"))
      (node (ref "C39") (pin "1") (pinfunction "1_1") (pintype "passive"))
      (node (ref "C4") (pin "2") (pinfunction "2_2") (pintype "passive"))
      (node (ref "C40") (pin "1") (pinfunction "1_1") (pintype "passive"))
      (node (ref "C41") (pin "1") (pinfunction "1_1") (pintype "passive"))
      (node (ref "C42") (pin "1") (pinfunction "1_1") (pintype "passive"))
      (node (ref "C43") (pin "1") (pinfunction "1_1") (pintype "passive"))
      (node (ref "C44") (pin "1") (pinfunction "1_1") (pintype "passive"))
      (node (ref "C45") (pin "1") (pinfunction "1_1") (pintype "passive"))
      (node (ref "C46") (pin "1") (pinfunction "1_1") (pintype "passive"))
      (node (ref "C47") (pin "1") (pinfunction "1_1") (pintype "passive"))
      (node (ref "C48") (pin "1") (pinfunction "1_1") (pintype "passive"))
      (node (ref "C49") (pin "1") (pinfunction "1_1") (pintype "passive"))
      (node (ref "C5") (pin "1") (pinfunction "1_1") (pintype "passive"))
      (node (ref "C50") (pin "1") (pinfunction "1_1") (pintype "passive"))
      (node (ref "C51") (pin "2") (pinfunction "2_2") (pintype "passive"))
      (node (ref "C52") (pin "1") (pinfunction "1_1") (pintype "passive"))
      (node (ref "C53") (pin "1") (pinfunction "1_1") (pintype "passive"))
      (node (ref "C54") (pin "1") (pinfunction "1_1") (pintype "passive"))
      (node (ref "C55") (pin "1") (pinfunction "1_1") (pintype "passive"))
      (node (ref "C56") (pin "1") (pinfunction "1_1") (pintype "passive"))
      (node (ref "C57") (pin "1") (pinfunction "1_1") (pintype "passive"))
      (node (ref "C58") (pin "2") (pinfunction "2_2") (pintype "passive"))
      (node (ref "C6") (pin "1") (pinfunction "1_1") (pintype "passive"))
      (node (ref "C7") (pin "1") (pinfunction "1_1") (pintype "passive"))
      (node (ref "C8") (pin "1") (pinfunction "1_1") (pintype "passive"))
      (node (ref "C9") (pin "1") (pinfunction "1_1") (pintype "passive"))
      (node (ref "CN1") (pin "4") (pinfunction "4_4") (pintype "passive"))
      (node (ref "D1") (pin "2") (pinfunction "A_2") (pintype "passive"))
      (node (ref "D2") (pin "1") (pinfunction "1_1") (pintype "passive"))
      (node (ref "D3") (pin "2") (pinfunction "A_2") (pintype "passive"))
      (node (ref "D4") (pin "2") (pinfunction "A_2") (pintype "passive"))
      (node (ref "IC1") (pin "7") (pinfunction "GND_7") (pintype "passive"))
      (node (ref "IC1") (pin "9") (pinfunction "EP_9") (pintype "passive"))
      (node (ref "IC2") (pin "2") (pinfunction "GND_2") (pintype "passive"))
      (node (ref "IC3") (pin "28") (pinfunction "AGND_28") (pintype "passive"))
      (node (ref "IC3") (pin "55") (pinfunction "EN_BUCK_55") (pintype "passive"))
      (node (ref "IC3") (pin "57") (pinfunction "GND_57") (pintype "passive"))
      (node (ref "J10") (pin "2") (pinfunction "2_2") (pintype "passive"))
      (node (ref "J11") (pin "2") (pinfunction "2_2") (pintype "passive"))
      (node (ref "J2") (pin "1") (pintype "passive"))
      (node (ref "J7") (pin "2") (pinfunction "2_2") (pintype "passive"))
      (node (ref "MOTOR_U4") (pin "1") (pintype "passive"))
      (node (ref "Q6") (pin "1") (pinfunction "S_1") (pintype "passive"))
      (node (ref "Q6") (pin "2") (pinfunction "S_2") (pintype "passive"))
      (node (ref "Q6") (pin "3") (pinfunction "S_3") (pintype "passive"))
      (node (ref "Q9") (pin "2") (pinfunction "E_2") (pintype "passive"))
      (node (ref "R11") (pin "2") (pinfunction "2_2") (pintype "passive"))
      (node (ref "R12") (pin "1") (pinfunction "1_1") (pintype "passive"))
      (node (ref "R20") (pin "1") (pinfunction "1_1") (pintype "passive"))
      (node (ref "R21") (pin "1") (pinfunction "1_1") (pintype "passive"))
      (node (ref "R28") (pin "2") (pinfunction "2_2") (pintype "passive"))
      (node (ref "R29") (pin "1") (pinfunction "1_1") (pintype "passive"))
      (node (ref "R31") (pin "1") (pinfunction "1_1") (pintype "passive"))
      (node (ref "R34") (pin "1") (pinfunction "1_1") (pintype "passive"))
      (node (ref "R8") (pin "1") (pinfunction "1_1") (pintype "passive"))
      (node (ref "SW1") (pin "2") (pinfunction "2_2") (pintype "passive"))
      (node (ref "U1") (pin "12") (pinfunction "VSSA_12") (pintype "passive"))
      (node (ref "U1") (pin "18") (pinfunction "VSS_18") (pintype "passive"))
      (node (ref "U1") (pin "63") (pinfunction "VSS_63") (pintype "passive"))
      (node (ref "X1") (pin "2") (pinfunction "GND_2") (pintype "passive"))
      (node (ref "X1") (pin "4") (pinfunction "GND_4") (pintype "passive"))
    )
    (net (code "43") (name "Net-(C10-Pad2)") (class "Default")
      (node (ref "C10") (pin "2") (pinfunction "2_2") (pintype "passive"))
      (node (ref "R1") (pin "1") (pinfunction "1_1") (pintype "passive"))
    )
    (net (code "44") (name "Net-(C11-Pad2)") (class "Default")
      (node (ref "C11") (pin "2") (pinfunction "2_2") (pintype "passive"))
      (node (ref "R2") (pin "1") (pinfunction "1_1") (pintype "passive"))
    )
    (net (code "45") (name "Net-(C12-Pad2)") (class "Default")
      (node (ref "C12") (pin "2") (pinfunction "2_2") (pintype "passive"))
      (node (ref "R3") (pin "1") (pinfunction "1_1") (pintype "passive"))
    )
    (net (code "46") (name "Net-(C17-Pad2)") (class "Default")
      (node (ref "C17") (pin "2") (pinfunction "2_2") (pintype "passive"))
      (node (ref "R16") (pin "1") (pinfunction "1_1") (pintype "passive"))
    )
    (net (code "47") (name "Net-(C18-Pad2)") (class "Default")
      (node (ref "C18") (pin "2") (pinfunction "2_2") (pintype "passive"))
      (node (ref "R17") (pin "1") (pinfunction "1_1") (pintype "passive"))
    )
    (net (code "48") (name "Net-(C19-Pad2)") (class "Default")
      (node (ref "C19") (pin "2") (pinfunction "2_2") (pintype "passive"))
      (node (ref "R18") (pin "1") (pinfunction "1_1") (pintype "passive"))
    )
    (net (code "49") (name "Net-(D1-K)") (class "Default")
      (node (ref "C3") (pin "1") (pinfunction "1_1") (pintype "passive"))
      (node (ref "D1") (pin "1") (pinfunction "K_1") (pintype "passive"))
      (node (ref "IC1") (pin "8") (pinfunction "SW_8") (pintype "passive"))
      (node (ref "L2") (pin "1") (pinfunction "1_1") (pintype "passive"))
    )
    (net (code "50") (name "Net-(IC1-BOOT)") (class "Default")
      (node (ref "C3") (pin "2") (pinfunction "2_2") (pintype "passive"))
      (node (ref "IC1") (pin "1") (pinfunction "BOOT_1") (pintype "passive"))
    )
    (net (code "51") (name "Net-(IC1-FB)") (class "Default")
      (node (ref "IC1") (pin "5") (pinfunction "FB_5") (pintype "passive"))
      (node (ref "R11") (pin "1") (pinfunction "1_1") (pintype "passive"))
      (node (ref "R4") (pin "1") (pinfunction "1_1") (pintype "passive"))
    )
    (net (code "52") (name "Net-(IC1-RT{slash}SYNC)") (class "Default")
      (node (ref "IC1") (pin "4") (pinfunction "RT/SYNC_4") (pintype "passive"))
      (node (ref "R8") (pin "2") (pinfunction "2_2") (pintype "passive"))
    )
    (net (code "53") (name "Net-(IC1-SS_or_PGOOD)") (class "Default")
      (node (ref "C9") (pin "2") (pinfunction "2_2") (pintype "passive"))
      (node (ref "IC1") (pin "6") (pinfunction "SS_or_PGOOD_6") (pintype "passive"))
    )
    (net (code "54") (name "Net-(IC2-EN)") (class "Default")
      (node (ref "IC2") (pin "3") (pinfunction "EN_3") (pintype "passive"))
      (node (ref "R19") (pin "1") (pinfunction "1_1") (pintype "passive"))
    )
    (net (code "55") (name "Net-(IC3-AVDD)") (class "Default")
      (node (ref "C31") (pin "1") (pinfunction "1_1") (pintype "passive"))
      (node (ref "IC3") (pin "27") (pinfunction "AVDD_27") (pintype "passive"))
    )
    (net (code "56") (name "Net-(IC3-BST_A)") (class "Default")
      (node (ref "C13") (pin "1") (pinfunction "1_1") (pintype "passive"))
      (node (ref "IC3") (pin "48") (pinfunction "BST_A_48") (pintype "passive"))
    )
    (net (code "57") (name "Net-(IC3-BST_B)") (class "Default")
      (node (ref "C15") (pin "1") (pinfunction "1_1") (pintype "passive"))
      (node (ref "IC3") (pin "43") (pinfunction "BST_B_43") (pintype "passive"))
    )
    (net (code "58") (name "Net-(IC3-BST_C)") (class "Default")
      (node (ref "C20") (pin "1") (pinfunction "1_1") (pintype "passive"))
      (node (ref "IC3") (pin "38") (pinfunction "BST_C_38") (pintype "passive"))
    )
    (net (code "59") (name "Net-(IC3-CP1)") (class "Default")
      (node (ref "C14") (pin "2") (pinfunction "2_2") (pintype "passive"))
      (node (ref "IC3") (pin "14") (pinfunction "CP1_14") (pintype "passive"))
    )
    (net (code "60") (name "Net-(IC3-CP2)") (class "Default")
      (node (ref "C14") (pin "1") (pinfunction "1_1") (pintype "passive"))
      (node (ref "IC3") (pin "15") (pinfunction "CP2_15") (pintype "passive"))
    )
    (net (code "61") (name "Net-(IC3-DTC)") (class "Default")
      (node (ref "IC3") (pin "7") (pinfunction "DTC_7") (pintype "passive"))
      (node (ref "R12") (pin "2") (pinfunction "2_2") (pintype "passive"))
    )
    (net (code "62") (name "Net-(IC3-DVDD)") (class "Default")
      (node (ref "C30") (pin "2") (pinfunction "2_2") (pintype "passive"))
      (node (ref "C48") (pin "2") (pinfunction "2_2") (pintype "passive"))
      (node (ref "IC3") (pin "23") (pinfunction "DVDD_23") (pintype "passive"))
    )
    (net (code "63") (name "Net-(IC3-GVDD)") (class "Default")
      (node (ref "C16") (pin "2") (pinfunction "2_2") (pintype "passive"))
      (node (ref "C41") (pin "2") (pinfunction "2_2") (pintype "passive"))
      (node (ref "IC3") (pin "13") (pinfunction "GVDD_13") (pintype "passive"))
    )
    (net (code "64") (name "Net-(IC3-SO1)") (class "Default")
      (node (ref "IC3") (pin "25") (pinfunction "SO1_25") (pintype "passive"))
      (node (ref "R22") (pin "1") (pinfunction "1_1") (pintype "passive"))
    )
    (net (code "65") (name "Net-(IC3-SO2)") (class "Default")
      (node (ref "IC3") (pin "26") (pinfunction "SO2_26") (pintype "passive"))
      (node (ref "R23") (pin "1") (pinfunction "1_1") (pintype "passive"))
    )
    (net (code "66") (name "Net-(IC3-nFAULT)") (class "Default")
      (node (ref "IC3") (pin "6") (pinfunction "nFAULT_6") (pintype "passive"))
      (node (ref "R9") (pin "1") (pinfunction "1_1") (pintype "passive"))
    )
    (net (code "67") (name "Net-(IC3-nOCTW)") (class "Default")
      (node (ref "IC3") (pin "5") (pinfunction "nOCTW_5") (pintype "passive"))
      (node (ref "R10") (pin "2") (pinfunction "2_2") (pintype "passive"))
    )
    (net (code "68") (name "Net-(Q1-G)") (class "Default")
      (node (ref "Q1") (pin "4") (pinfunction "G_4") (pintype "passive"))
      (node (ref "R5") (pin "2") (pinfunction "2_2") (pintype "passive"))
    )
    (net (code "69") (name "Net-(Q2-G)") (class "Default")
      (node (ref "Q2") (pin "4") (pinfunction "G_4") (pintype "passive"))
      (node (ref "R7") (pin "2") (pinfunction "2_2") (pintype "passive"))
    )
    (net (code "70") (name "Net-(Q3-G)") (class "Default")
      (node (ref "Q3") (pin "4") (pinfunction "G_4") (pintype "passive"))
      (node (ref "R6") (pin "2") (pinfunction "2_2") (pintype "passive"))
    )
    (net (code "71") (name "Net-(Q4-G)") (class "Default")
      (node (ref "Q4") (pin "4") (pinfunction "G_4") (pintype "passive"))
      (node (ref "R13") (pin "2") (pinfunction "2_2") (pintype "passive"))
    )
    (net (code "72") (name "Net-(Q5-G)") (class "Default")
      (node (ref "Q5") (pin "4") (pinfunction "G_4") (pintype "passive"))
      (node (ref "R14") (pin "2") (pinfunction "2_2") (pintype "passive"))
    )
    (net (code "73") (name "Net-(Q6-G)") (class "Default")
      (node (ref "Q6") (pin "4") (pinfunction "G_4") (pintype "passive"))
      (node (ref "R15") (pin "2") (pinfunction "2_2") (pintype "passive"))
    )
    (net (code "74") (name "Net-(U1A-BOOT0)") (class "Default")
      (node (ref "R31") (pin "2") (pinfunction "2_2") (pintype "passive"))
      (node (ref "U1") (pin "60") (pinfunction "BOOT0_60") (pintype "passive"))
    )
    (net (code "75") (name "Net-(U1A-PB2-BOOT1(PB2))") (class "Default")
      (node (ref "R28") (pin "1") (pinfunction "1_1") (pintype "passive"))
      (node (ref "U1") (pin "28") (pinfunction "PB2-BOOT1(PB2)_28") (pintype "passive"))
    )
    (net (code "76") (name "Net-(U1A-VCAP_1)") (class "Default")
      (node (ref "C55") (pin "2") (pinfunction "2_2") (pintype "passive"))
      (node (ref "U1") (pin "31") (pinfunction "VCAP_1_31") (pintype "passive"))
    )
    (net (code "77") (name "Net-(U1A-VCAP_2)") (class "Default")
      (node (ref "C56") (pin "2") (pinfunction "2_2") (pintype "passive"))
      (node (ref "U1") (pin "47") (pinfunction "VCAP_2_47") (pintype "passive"))
    )
    (net (code "78") (name "POWER_BUCK") (class "Default")
      (node (ref "C4") (pin "1") (pinfunction "1_1") (pintype "passive"))
      (node (ref "IC1") (pin "2") (pinfunction "VIN_2") (pintype "passive"))
      (node (ref "L1") (pin "2") (pinfunction "2_2") (pintype "passive"))
      (node (ref "R26") (pin "2") (pinfunction "2_2") (pintype "passive"))
    )
    (net (code "79") (name "POWER_IN") (class "Default")
      (node (ref "C21") (pin "2") (pinfunction "2_2") (pintype "passive"))
      (node (ref "C34") (pin "2") (pinfunction "2_2") (pintype "passive"))
      (node (ref "C35") (pin "2") (pinfunction "2_2") (pintype "passive"))
      (node (ref "C36") (pin "2") (pinfunction "2_2") (pintype "passive"))
      (node (ref "C37") (pin "2") (pinfunction "2_2") (pintype "passive"))
      (node (ref "C38") (pin "2") (pinfunction "2_2") (pintype "passive"))
      (node (ref "C39") (pin "2") (pinfunction "2_2") (pintype "passive"))
      (node (ref "C40") (pin "2") (pinfunction "2_2") (pintype "passive"))
      (node (ref "C49") (pin "2") (pinfunction "2_2") (pintype "passive"))
      (node (ref "C5") (pin "2") (pinfunction "2_2") (pintype "passive"))
      (node (ref "C50") (pin "2") (pinfunction "2_2") (pintype "passive"))
      (node (ref "C52") (pin "2") (pinfunction "2_2") (pintype "passive"))
      (node (ref "C8") (pin "2") (pinfunction "2_2") (pintype "passive"))
      (node (ref "D2") (pin "2") (pinfunction "2_2") (pintype "passive"))
      (node (ref "D3") (pin "1") (pinfunction "K_1") (pintype "passive"))
      (node (ref "IC3") (pin "29") (pinfunction "PVDD1_29") (pintype "passive"))
      (node (ref "J1") (pin "1") (pintype "passive"))
      (node (ref "L1") (pin "1") (pinfunction "1_1") (pintype "passive"))
      (node (ref "Q1") (pin "5") (pinfunction "D_5") (pintype "passive"))
      (node (ref "Q1") (pin "6") (pinfunction "D_6") (pintype "passive"))
      (node (ref "Q1") (pin "7") (pinfunction "D_7") (pintype "passive"))
      (node (ref "Q1") (pin "8") (pinfunction "D_8") (pintype "passive"))
      (node (ref "Q1") (pin "9") (pinfunction "D_9") (pintype "passive"))
      (node (ref "Q2") (pin "5") (pinfunction "D_5") (pintype "passive"))
      (node (ref "Q2") (pin "6") (pinfunction "D_6") (pintype "passive"))
      (node (ref "Q2") (pin "7") (pinfunction "D_7") (pintype "passive"))
      (node (ref "Q2") (pin "8") (pinfunction "D_8") (pintype "passive"))
      (node (ref "Q2") (pin "9") (pinfunction "D_9") (pintype "passive"))
      (node (ref "Q3") (pin "5") (pinfunction "D_5") (pintype "passive"))
      (node (ref "Q3") (pin "6") (pinfunction "D_6") (pintype "passive"))
      (node (ref "Q3") (pin "7") (pinfunction "D_7") (pintype "passive"))
      (node (ref "Q3") (pin "8") (pinfunction "D_8") (pintype "passive"))
      (node (ref "Q3") (pin "9") (pinfunction "D_9") (pintype "passive"))
      (node (ref "R1") (pin "2") (pinfunction "2_2") (pintype "passive"))
      (node (ref "R2") (pin "2") (pinfunction "2_2") (pintype "passive"))
      (node (ref "R3") (pin "2") (pinfunction "2_2") (pintype "passive"))
    )
    (net (code "80") (name "V_5V") (class "Default")
      (node (ref "C22") (pin "2") (pinfunction "2_2") (pintype "passive"))
      (node (ref "C6") (pin "2") (pinfunction "2_2") (pintype "passive"))
      (node (ref "C7") (pin "2") (pinfunction "2_2") (pintype "passive"))
      (node (ref "D4") (pin "1") (pinfunction "K_1") (pintype "passive"))
      (node (ref "IC2") (pin "1") (pinfunction "VIN_1") (pintype "passive"))
      (node (ref "L2") (pin "2") (pinfunction "2_2") (pintype "passive"))
      (node (ref "R19") (pin "2") (pinfunction "2_2") (pintype "passive"))
      (node (ref "R4") (pin "2") (pinfunction "2_2") (pintype "passive"))
    )
    (net (code "81") (name "unconnected-(IC2-NC-Pad4)") (class "Default")
      (node (ref "IC2") (pin "4") (pinfunction "NC_4") (pintype "passive+no_connect"))
    )
    (net (code "82") (name "unconnected-(IC3-BST_BK-Pad52)") (class "Default")
      (node (ref "IC3") (pin "52") (pinfunction "BST_BK_52") (pintype "passive+no_connect"))
    )
    (net (code "83") (name "unconnected-(IC3-COMP-Pad2)") (class "Default")
      (node (ref "IC3") (pin "2") (pinfunction "COMP_2") (pintype "passive+no_connect"))
    )
    (net (code "84") (name "unconnected-(IC3-PH-Pad50)") (class "Default")
      (node (ref "IC3") (pin "50") (pinfunction "PH_50") (pintype "passive+no_connect"))
    )
    (net (code "85") (name "unconnected-(IC3-PH-Pad51)") (class "Default")
      (node (ref "IC3") (pin "51") (pinfunction "PH_51") (pintype "passive+no_connect"))
    )
    (net (code "86") (name "unconnected-(IC3-PVDD2-Pad53)") (class "Default")
      (node (ref "IC3") (pin "53") (pinfunction "PVDD2_53") (pintype "passive+no_connect"))
    )
    (net (code "87") (name "unconnected-(IC3-PVDD2-Pad54)") (class "Default")
      (node (ref "IC3") (pin "54") (pinfunction "PVDD2_54") (pintype "passive+no_connect"))
    )
    (net (code "88") (name "unconnected-(IC3-PWRGD-Pad4)") (class "Default")
      (node (ref "IC3") (pin "4") (pinfunction "PWRGD_4") (pintype "passive+no_connect"))
    )
    (net (code "89") (name "unconnected-(IC3-RT_CLK-Pad1)") (class "Default")
      (node (ref "IC3") (pin "1") (pinfunction "RT_CLK_1") (pintype "passive+no_connect"))
    )
    (net (code "90") (name "unconnected-(IC3-SS_TR-Pad56)") (class "Default")
      (node (ref "IC3") (pin "56") (pinfunction "SS_TR_56") (pintype "passive+no_connect"))
    )
    (net (code "91") (name "unconnected-(IC3-VSENSE-Pad3)") (class "Default")
      (node (ref "IC3") (pin "3") (pinfunction "VSENSE_3") (pintype "passive+no_connect"))
    )
    (net (code "92") (name "unconnected-(U1A-PA2-Pad16)") (class "Default")
      (node (ref "U1") (pin "16") (pinfunction "PA2_16") (pintype "passive+no_connect"))
    )
    (net (code "93") (name "unconnected-(U1A-PA3-Pad17)") (class "Default")
      (node (ref "U1") (pin "17") (pinfunction "PA3_17") (pintype "passive+no_connect"))
    )
    (net (code "94") (name "unconnected-(U1A-PA5-Pad21)") (class "Default")
      (node (ref "U1") (pin "21") (pinfunction "PA5_21") (pintype "passive+no_connect"))
    )
    (net (code "95") (name "unconnected-(U1A-PA7-Pad23)") (class "Default")
      (node (ref "U1") (pin "23") (pinfunction "PA7_23") (pintype "passive+no_connect"))
    )
    (net (code "96") (name "unconnected-(U1A-PA11-Pad44)") (class "Default")
      (node (ref "U1") (pin "44") (pinfunction "PA11_44") (pintype "passive+no_connect"))
    )
    (net (code "97") (name "unconnected-(U1A-PA12-Pad45)") (class "Default")
      (node (ref "U1") (pin "45") (pinfunction "PA12_45") (pintype "passive+no_connect"))
    )
    (net (code "98") (name "unconnected-(U1A-PA15(JTDI)-Pad50)") (class "Default")
      (node (ref "U1") (pin "50") (pinfunction "PA15(JTDI)_50") (pintype "passive+no_connect"))
    )
    (net (code "99") (name "unconnected-(U1A-PB0-Pad26)") (class "Default")
      (node (ref "U1") (pin "26") (pinfunction "PB0_26") (pintype "passive+no_connect"))
    )
    (net (code "100") (name "unconnected-(U1A-PB1-Pad27)") (class "Default")
      (node (ref "U1") (pin "27") (pinfunction "PB1_27") (pintype "passive+no_connect"))
    )
    (net (code "101") (name "unconnected-(U1A-PB3(JTDOTRACESWO)-Pad55)") (class "Default")
      (node (ref "U1") (pin "55") (pinfunction "PB3(JTDOTRACESWO)_55") (pintype "passive+no_connect"))
    )
    (net (code "102") (name "unconnected-(U1A-PB4(NJTRST)-Pad56)") (class "Default")
      (node (ref "U1") (pin "56") (pinfunction "PB4(NJTRST)_56") (pintype "passive+no_connect"))
    )
    (net (code "103") (name "unconnected-(U1A-PB5-Pad57)") (class "Default")
      (node (ref "U1") (pin "57") (pinfunction "PB5_57") (pintype "passive+no_connect"))
    )
    (net (code "104") (name "unconnected-(U1A-PB7-Pad59)") (class "Default")
      (node (ref "U1") (pin "59") (pinfunction "PB7_59") (pintype "passive+no_connect"))
    )
    (net (code "105") (name "unconnected-(U1A-PB8-Pad61)") (class "Default")
      (node (ref "U1") (pin "61") (pinfunction "PB8_61") (pintype "passive+no_connect"))
    )
    (net (code "106") (name "unconnected-(U1A-PB9-Pad62)") (class "Default")
      (node (ref "U1") (pin "62") (pinfunction "PB9_62") (pintype "passive+no_connect"))
    )
    (net (code "107") (name "unconnected-(U1A-PB10-Pad29)") (class "Default")
      (node (ref "U1") (pin "29") (pinfunction "PB10_29") (pintype "passive+no_connect"))
    )
    (net (code "108") (name "unconnected-(U1A-PB11-Pad30)") (class "Default")
      (node (ref "U1") (pin "30") (pinfunction "PB11_30") (pintype "passive+no_connect"))
    )
    (net (code "109") (name "unconnected-(U1A-PB12-Pad33)") (class "Default")
      (node (ref "U1") (pin "33") (pinfunction "PB12_33") (pintype "passive+no_connect"))
    )
    (net (code "110") (name "unconnected-(U1A-PC0-Pad8)") (class "Default")
      (node (ref "U1") (pin "8") (pinfunction "PC0_8") (pintype "passive+no_connect"))
    )
    (net (code "111") (name "unconnected-(U1A-PC1-Pad9)") (class "Default")
      (node (ref "U1") (pin "9") (pinfunction "PC1_9") (pintype "passive+no_connect"))
    )
    (net (code "112") (name "unconnected-(U1A-PC4-Pad24)") (class "Default")
      (node (ref "U1") (pin "24") (pinfunction "PC4_24") (pintype "passive+no_connect"))
    )
    (net (code "113") (name "unconnected-(U1A-PC5-Pad25)") (class "Default")
      (node (ref "U1") (pin "25") (pinfunction "PC5_25") (pintype "passive+no_connect"))
    )
    (net (code "114") (name "unconnected-(U1A-PC7-Pad38)") (class "Default")
      (node (ref "U1") (pin "38") (pinfunction "PC7_38") (pintype "passive+no_connect"))
    )
    (net (code "115") (name "unconnected-(U1A-PC8-Pad39)") (class "Default")
      (node (ref "U1") (pin "39") (pinfunction "PC8_39") (pintype "passive+no_connect"))
    )
    (net (code "116") (name "unconnected-(U1A-PC9-Pad40)") (class "Default")
      (node (ref "U1") (pin "40") (pinfunction "PC9_40") (pintype "passive+no_connect"))
    )
    (net (code "117") (name "unconnected-(U1A-PC13-Pad2)") (class "Default")
      (node (ref "U1") (pin "2") (pinfunction "PC13_2") (pintype "passive+no_connect"))
    )
    (net (code "118") (name "unconnected-(U1A-PC14-OSC32_IN(PC14)-Pad3)") (class "Default")
      (node (ref "U1") (pin "3") (pinfunction "PC14-OSC32_IN(PC14)_3") (pintype "passive+no_connect"))
    )
    (net (code "119") (name "unconnected-(U1A-PC15-OSC32_OUT(PC15)-Pad4)") (class "Default")
      (node (ref "U1") (pin "4") (pinfunction "PC15-OSC32_OUT(PC15)_4") (pintype "passive+no_connect"))
    )
    (net (code "120") (name "unconnected-(U1A-PD2-Pad54)") (class "Default")
      (node (ref "U1") (pin "54") (pinfunction "PD2_54") (pintype "passive+no_connect"))
    )
  )
)
